# SB_TS_2_00.net
KiCad netlist of a schematic drawn in EAGLE
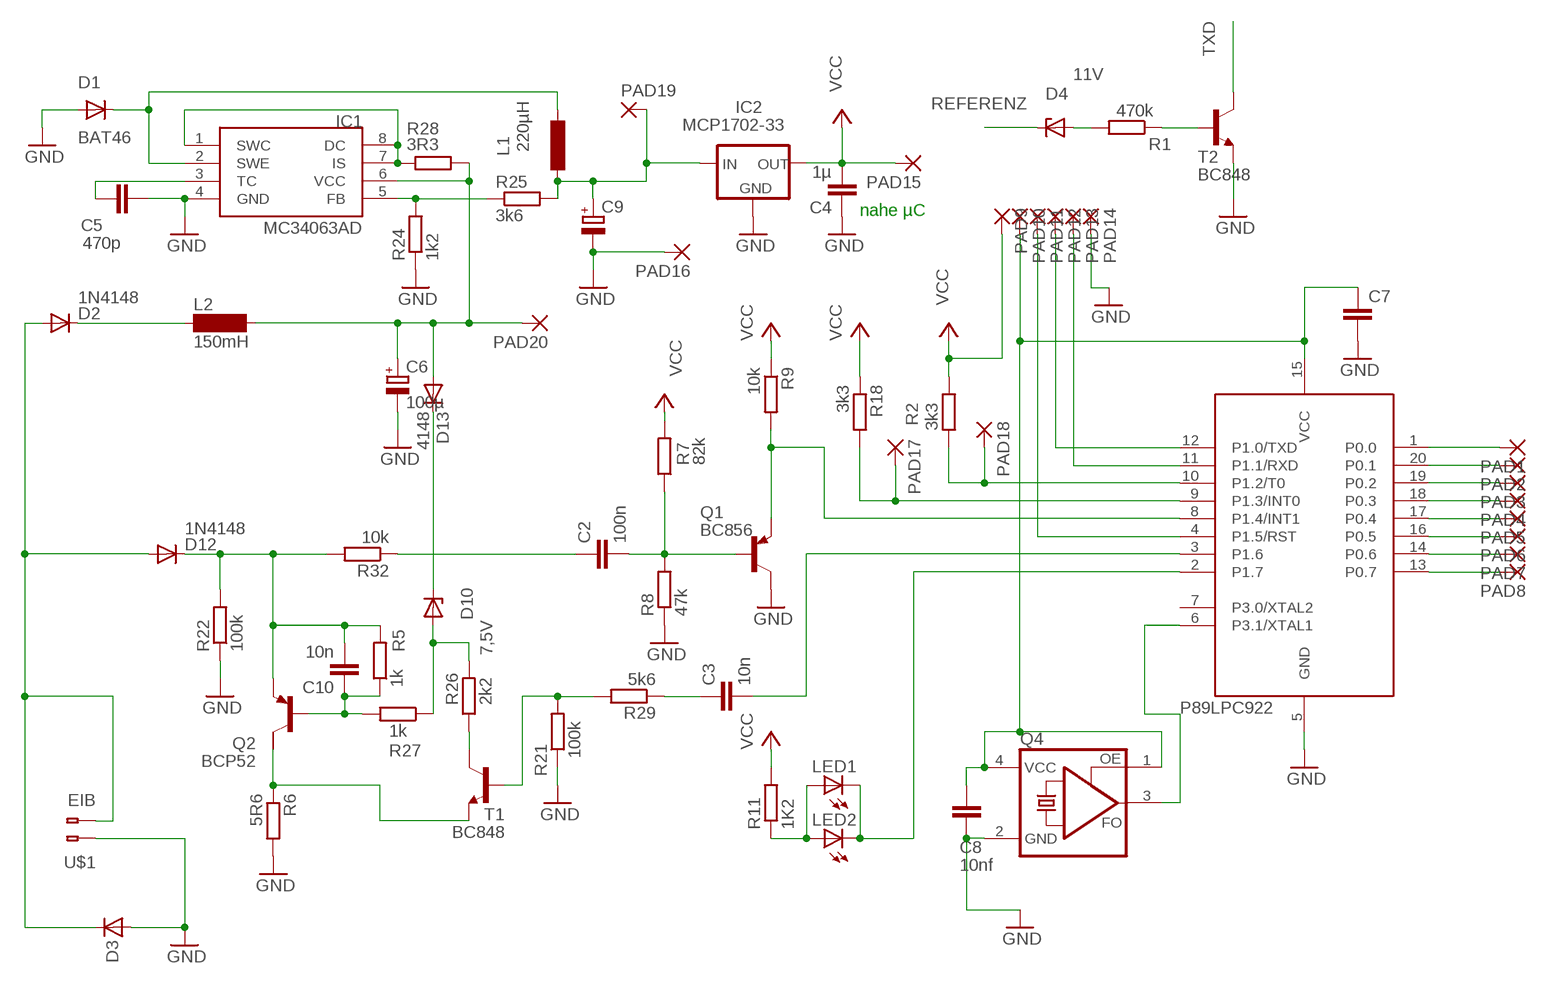
[diagram p0: schematic, sheet 1]

(export (version "E")
  (design (tool "Eeschema 10.0.6"))
  (components
    (comp (ref "C2")
      (value "100n")
      (footprint "eagle-import:C1206")
      (libsource (lib "eagle-import") (part "C-EUC1206"))
    )
    (comp (ref "C3")
      (value "10n")
      (footprint "eagle-import:C1206")
      (libsource (lib "eagle-import") (part "C-EUC1206"))
    )
    (comp (ref "C4")
      (value "1µ")
      (footprint "eagle-import:C1206")
      (libsource (lib "eagle-import") (part "C-EUC1206"))
    )
    (comp (ref "C5")
      (value "470p")
      (footprint "eagle-import:C1206")
      (libsource (lib "eagle-import") (part "C-EUC1206"))
    )
    (comp (ref "C6")
      (value "100µ")
      (footprint "eagle-import:SANYO-OSCON_SMD_C6")
      (libsource (lib "eagle-import") (part "CPOL-EUSANYO_SMD_C6"))
    )
    (comp (ref "C7")
      (value "C-EUC1206")
      (footprint "eagle-import:C1206")
      (libsource (lib "eagle-import") (part "C-EUC1206"))
    )
    (comp (ref "C8")
      (value "10nf")
      (footprint "eagle-import:C1206")
      (libsource (lib "eagle-import") (part "C-EUC1206"))
    )
    (comp (ref "C9")
      (value "CPOL-EUE2.5-5")
      (footprint "eagle-import:E2,5-5")
      (libsource (lib "eagle-import") (part "CPOL-EUE2.5-5"))
    )
    (comp (ref "C10")
      (value "10n")
      (footprint "eagle-import:C1206")
      (libsource (lib "eagle-import") (part "C-EUC1206"))
    )
    (comp (ref "D1")
      (value "BAT46")
      (footprint "eagle-import:MINIMELF")
      (libsource (lib "eagle-import") (part "DIODE-MINIMELF"))
    )
    (comp (ref "D2")
      (value "1N4148")
      (footprint "eagle-import:MINIMELF")
      (libsource (lib "eagle-import") (part "DIODE-MINIMELF"))
    )
    (comp (ref "D3")
      (value "SMAJ40AC")
      (footprint "eagle-import:SMB")
      (libsource (lib "eagle-import") (part "D-SMB"))
    )
    (comp (ref "D4")
      (value "11V")
      (footprint "eagle-import:MINIMELF")
      (libsource (lib "eagle-import") (part "ZPD"))
    )
    (comp (ref "D10")
      (value "7,5V")
      (footprint "eagle-import:MINIMELF")
      (libsource (lib "eagle-import") (part "ZPD"))
    )
    (comp (ref "D12")
      (value "1N4148")
      (footprint "eagle-import:MINIMELF")
      (libsource (lib "eagle-import") (part "DIODE-MINIMELF"))
    )
    (comp (ref "D13")
      (value "4148")
      (footprint "eagle-import:MINIMELF")
      (libsource (lib "eagle-import") (part "DIODE-MINIMELF"))
    )
    (comp (ref "IC1")
      (value "MC34063AD")
      (footprint "eagle-import:SOIC8")
      (libsource (lib "eagle-import") (part "MC34063AD"))
    )
    (comp (ref "IC2")
      (value "MCP1702-33")
      (footprint "eagle-import:79LXX")
      (libsource (lib "eagle-import") (part "79LXX"))
    )
    (comp (ref "IC3")
      (value "LPC922FDH")
      (footprint "eagle-import:TSSOP20")
      (libsource (lib "eagle-import") (part "LPC922FDH"))
    )
    (comp (ref "L1")
      (value "220µH")
      (footprint "eagle-import:2200-11.43")
      (libsource (lib "eagle-import") (part "L-EU2200-11.43"))
    )
    (comp (ref "L2")
      (value "150mH")
      (footprint "eagle-import:SD12_1000")
      (libsource (lib "eagle-import") (part "SD12-1000"))
    )
    (comp (ref "LED1")
      (value "LEDCHIPLED_1206")
      (footprint "eagle-import:CHIPLED_1206")
      (libsource (lib "eagle-import") (part "LEDCHIPLED_1206"))
    )
    (comp (ref "LED2")
      (value "LED3MM")
      (footprint "eagle-import:LED3MM")
      (libsource (lib "eagle-import") (part "LED3MM"))
    )
    (comp (ref "PAD1")
      (value "SMD2")
      (footprint "eagle-import:SMD1,27-2,54")
      (libsource (lib "eagle-import") (part "SMD2"))
    )
    (comp (ref "PAD2")
      (value "SMD2")
      (footprint "eagle-import:SMD1,27-2,54")
      (libsource (lib "eagle-import") (part "SMD2"))
    )
    (comp (ref "PAD3")
      (value "SMD2")
      (footprint "eagle-import:SMD1,27-2,54")
      (libsource (lib "eagle-import") (part "SMD2"))
    )
    (comp (ref "PAD4")
      (value "SMD2")
      (footprint "eagle-import:SMD1,27-2,54")
      (libsource (lib "eagle-import") (part "SMD2"))
    )
    (comp (ref "PAD5")
      (value "SMD2")
      (footprint "eagle-import:SMD1,27-2,54")
      (libsource (lib "eagle-import") (part "SMD2"))
    )
    (comp (ref "PAD6")
      (value "SMD2")
      (footprint "eagle-import:SMD1,27-2,54")
      (libsource (lib "eagle-import") (part "SMD2"))
    )
    (comp (ref "PAD7")
      (value "SMD2")
      (footprint "eagle-import:SMD1,27-2,54")
      (libsource (lib "eagle-import") (part "SMD2"))
    )
    (comp (ref "PAD8")
      (value "SMD2")
      (footprint "eagle-import:SMD1,27-2,54")
      (libsource (lib "eagle-import") (part "SMD2"))
    )
    (comp (ref "PAD9")
      (value "SMD2")
      (footprint "eagle-import:SMD1,27-2,54")
      (libsource (lib "eagle-import") (part "SMD2"))
    )
    (comp (ref "PAD10")
      (value "SMD2")
      (footprint "eagle-import:SMD1,27-2,54")
      (libsource (lib "eagle-import") (part "SMD2"))
    )
    (comp (ref "PAD11")
      (value "SMD2")
      (footprint "eagle-import:SMD1,27-2,54")
      (libsource (lib "eagle-import") (part "SMD2"))
    )
    (comp (ref "PAD12")
      (value "SMD2")
      (footprint "eagle-import:SMD1,27-2,54")
      (libsource (lib "eagle-import") (part "SMD2"))
    )
    (comp (ref "PAD13")
      (value "SMD2")
      (footprint "eagle-import:SMD1,27-2,54")
      (libsource (lib "eagle-import") (part "SMD2"))
    )
    (comp (ref "PAD14")
      (value "SMD2")
      (footprint "eagle-import:SMD1,27-2,54")
      (libsource (lib "eagle-import") (part "SMD2"))
    )
    (comp (ref "PAD15")
      (value "SMD2")
      (footprint "eagle-import:SMD1,27-2,54")
      (libsource (lib "eagle-import") (part "SMD2"))
    )
    (comp (ref "PAD16")
      (value "SMD2")
      (footprint "eagle-import:SMD1,27-2,54")
      (libsource (lib "eagle-import") (part "SMD2"))
    )
    (comp (ref "PAD17")
      (value "SMD2")
      (footprint "eagle-import:SMD1,27-2,54")
      (libsource (lib "eagle-import") (part "SMD2"))
    )
    (comp (ref "PAD18")
      (value "SMD2")
      (footprint "eagle-import:SMD1,27-2,54")
      (libsource (lib "eagle-import") (part "SMD2"))
    )
    (comp (ref "PAD19")
      (value "SMD2")
      (footprint "eagle-import:SMD1,27-2,54")
      (libsource (lib "eagle-import") (part "SMD2"))
    )
    (comp (ref "PAD20")
      (value "SMD2")
      (footprint "eagle-import:SMD1,27-2,54")
      (libsource (lib "eagle-import") (part "SMD2"))
    )
    (comp (ref "Q1")
      (value "BC856")
      (footprint "eagle-import:SOT23-BEC")
      (libsource (lib "eagle-import") (part "BC856SMDALT1"))
    )
    (comp (ref "Q2")
      (value "BCP52")
      (footprint "eagle-import:SOT223")
      (libsource (lib "eagle-import") (part "FZT753SMD"))
    )
    (comp (ref "Q4")
      (value "ASFL")
      (footprint "eagle-import:ASF")
      (libsource (lib "eagle-import") (part "ASFL"))
    )
    (comp (ref "R1")
      (value "470k")
      (footprint "eagle-import:R1206")
      (libsource (lib "eagle-import") (part "R-EU_R1206"))
    )
    (comp (ref "R2")
      (value "3k3")
      (footprint "eagle-import:M1206")
      (libsource (lib "eagle-import") (part "R-EU_M1206"))
    )
    (comp (ref "R5")
      (value "1k")
      (footprint "eagle-import:R1206")
      (libsource (lib "eagle-import") (part "R-EU_R1206"))
    )
    (comp (ref "R6")
      (value "5R6")
      (footprint "eagle-import:R1206")
      (libsource (lib "eagle-import") (part "R-EU_R1206"))
    )
    (comp (ref "R7")
      (value "82k")
      (footprint "eagle-import:R1206")
      (libsource (lib "eagle-import") (part "R-EU_R1206"))
    )
    (comp (ref "R8")
      (value "47k")
      (footprint "eagle-import:M1206")
      (libsource (lib "eagle-import") (part "R-EU_M1206"))
    )
    (comp (ref "R9")
      (value "10k")
      (footprint "eagle-import:R1206")
      (libsource (lib "eagle-import") (part "R-EU_R1206"))
    )
    (comp (ref "R11")
      (value "1K2")
      (footprint "eagle-import:R1206")
      (libsource (lib "eagle-import") (part "R-EU_R1206"))
    )
    (comp (ref "R18")
      (value "3k3")
      (footprint "eagle-import:R1206")
      (libsource (lib "eagle-import") (part "R-EU_R1206"))
    )
    (comp (ref "R21")
      (value "100k")
      (footprint "eagle-import:R1206")
      (libsource (lib "eagle-import") (part "R-EU_R1206"))
    )
    (comp (ref "R22")
      (value "100k")
      (footprint "eagle-import:M1206")
      (libsource (lib "eagle-import") (part "R-EU_M1206"))
    )
    (comp (ref "R24")
      (value "1k2")
      (footprint "eagle-import:R1206")
      (libsource (lib "eagle-import") (part "R-EU_R1206"))
    )
    (comp (ref "R25")
      (value "3k6")
      (footprint "eagle-import:M1206")
      (libsource (lib "eagle-import") (part "R-EU_M1206"))
    )
    (comp (ref "R26")
      (value "2k2")
      (footprint "eagle-import:M1206")
      (libsource (lib "eagle-import") (part "R-EU_M1206"))
    )
    (comp (ref "R27")
      (value "1k")
      (footprint "eagle-import:R1206")
      (libsource (lib "eagle-import") (part "R-EU_R1206"))
    )
    (comp (ref "R28")
      (value "3R3")
      (footprint "eagle-import:M1206")
      (libsource (lib "eagle-import") (part "R-EU_M1206"))
    )
    (comp (ref "R29")
      (value "5k6")
      (footprint "eagle-import:R1206")
      (libsource (lib "eagle-import") (part "R-EU_R1206"))
    )
    (comp (ref "R32")
      (value "10k")
      (footprint "eagle-import:R1206")
      (libsource (lib "eagle-import") (part "R-EU_R1206"))
    )
    (comp (ref "T1")
      (value "BC848")
      (footprint "eagle-import:SOT23")
      (libsource (lib "eagle-import") (part "BC848"))
    )
    (comp (ref "T2")
      (value "BC848")
      (footprint "eagle-import:SOT23")
      (libsource (lib "eagle-import") (part "BC848"))
    )
    (comp (ref "U$1")
      (value "EIB")
      (footprint "eagle-import:BUSKLEMME243-724")
      (libsource (lib "eagle-import") (part "EIB"))
    )
  )
  (nets
    (net (code "1") (name "/REFERENZ") (class "Default")
      (node (ref "D10") (pin "A") (pinfunction "A_A") (pintype "passive"))
      (node (ref "D4") (pin "C") (pinfunction "C_C") (pintype "passive"))
      (node (ref "R26") (pin "2") (pinfunction "2_2") (pintype "passive"))
      (node (ref "R27") (pin "1") (pinfunction "1_1") (pintype "passive"))
    )
    (net (code "2") (name "/TXD") (class "Default")
      (node (ref "IC3") (pin "12") (pinfunction "P1.0/TXD_12") (pintype "bidirectional"))
      (node (ref "PAD12") (pin "1") (pinfunction "P_1") (pintype "passive"))
      (node (ref "T2") (pin "3") (pinfunction "C_3") (pintype "passive"))
    )
    (net (code "3") (name "GND") (class "Default")
      (node (ref "C4") (pin "1") (pinfunction "1_1") (pintype "passive"))
      (node (ref "C5") (pin "2") (pinfunction "2_2") (pintype "passive"))
      (node (ref "C6") (pin "-") (pinfunction "-_-") (pintype "passive"))
      (node (ref "C7") (pin "2") (pinfunction "2_2") (pintype "passive"))
      (node (ref "C8") (pin "2") (pinfunction "2_2") (pintype "passive"))
      (node (ref "C9") (pin "-") (pinfunction "-_-") (pintype "passive"))
      (node (ref "D1") (pin "A") (pinfunction "A_A") (pintype "passive"))
      (node (ref "D3") (pin "2") (pinfunction "A_2") (pintype "passive"))
      (node (ref "IC1") (pin "4") (pinfunction "GND_4") (pintype "passive"))
      (node (ref "IC2") (pin "GND") (pinfunction "GND_GND") (pintype "input"))
      (node (ref "IC3") (pin "5") (pinfunction "GND_5") (pintype "bidirectional"))
      (node (ref "PAD14") (pin "1") (pinfunction "P_1") (pintype "passive"))
      (node (ref "PAD16") (pin "1") (pinfunction "P_1") (pintype "passive"))
      (node (ref "Q1") (pin "C") (pinfunction "C_C") (pintype "passive"))
      (node (ref "Q4") (pin "2") (pinfunction "GND_2") (pintype "power_in"))
      (node (ref "R21") (pin "1") (pinfunction "1_1") (pintype "passive"))
      (node (ref "R22") (pin "1") (pinfunction "1_1") (pintype "passive"))
      (node (ref "R24") (pin "1") (pinfunction "1_1") (pintype "passive"))
      (node (ref "R6") (pin "2") (pinfunction "2_2") (pintype "passive"))
      (node (ref "R8") (pin "1") (pinfunction "1_1") (pintype "passive"))
      (node (ref "T2") (pin "2") (pinfunction "E_2") (pintype "passive"))
      (node (ref "U$1") (pin "1") (pinfunction "B-1_1") (pintype "passive"))
    )
    (net (code "4") (name "Net-(C2-Pad1)") (class "Default")
      (node (ref "C2") (pin "1") (pinfunction "1_1") (pintype "passive"))
      (node (ref "R32") (pin "1") (pinfunction "1_1") (pintype "passive"))
    )
    (net (code "5") (name "Net-(C2-Pad2)") (class "Default")
      (node (ref "C2") (pin "2") (pinfunction "2_2") (pintype "passive"))
      (node (ref "Q1") (pin "B") (pinfunction "B_B") (pintype "passive"))
      (node (ref "R7") (pin "1") (pinfunction "1_1") (pintype "passive"))
      (node (ref "R8") (pin "2") (pinfunction "2_2") (pintype "passive"))
    )
    (net (code "6") (name "Net-(C3-Pad1)") (class "Default")
      (node (ref "C3") (pin "1") (pinfunction "1_1") (pintype "passive"))
      (node (ref "R29") (pin "1") (pinfunction "1_1") (pintype "passive"))
    )
    (net (code "7") (name "Net-(D2-PadC)") (class "Default")
      (node (ref "D2") (pin "C") (pinfunction "C_C") (pintype "passive"))
      (node (ref "L2") (pin "1") (pinfunction "1_1") (pintype "passive"))
    )
    (net (code "8") (name "Net-(D3-C)") (class "Default")
      (node (ref "D12") (pin "A") (pinfunction "A_A") (pintype "passive"))
      (node (ref "D2") (pin "A") (pinfunction "A_A") (pintype "passive"))
      (node (ref "D3") (pin "1") (pinfunction "C_1") (pintype "passive"))
      (node (ref "U$1") (pin "2") (pinfunction "B-2_2") (pintype "passive"))
    )
    (net (code "9") (name "Net-(D4-PadA)") (class "Default")
      (node (ref "D4") (pin "A") (pinfunction "A_A") (pintype "passive"))
      (node (ref "R1") (pin "2") (pinfunction "2_2") (pintype "passive"))
    )
    (net (code "10") (name "Net-(D10-PadC)") (class "Default")
      (node (ref "D10") (pin "C") (pinfunction "C_C") (pintype "passive"))
      (node (ref "D13") (pin "C") (pinfunction "C_C") (pintype "passive"))
    )
    (net (code "11") (name "Net-(IC1-DC)") (class "Default")
      (node (ref "IC1") (pin "1") (pinfunction "SWC_1") (pintype "passive"))
      (node (ref "IC1") (pin "7") (pinfunction "IS_7") (pintype "passive"))
      (node (ref "IC1") (pin "8") (pinfunction "DC_8") (pintype "passive"))
      (node (ref "R28") (pin "1") (pinfunction "1_1") (pintype "passive"))
    )
    (net (code "12") (name "Net-(IC1-FB)") (class "Default")
      (node (ref "IC1") (pin "5") (pinfunction "FB_5") (pintype "passive"))
      (node (ref "R24") (pin "2") (pinfunction "2_2") (pintype "passive"))
      (node (ref "R25") (pin "1") (pinfunction "1_1") (pintype "passive"))
    )
    (net (code "13") (name "Net-(IC1-SWE)") (class "Default")
      (node (ref "D1") (pin "C") (pinfunction "C_C") (pintype "passive"))
      (node (ref "IC1") (pin "2") (pinfunction "SWE_2") (pintype "passive"))
      (node (ref "L1") (pin "2") (pinfunction "2_2") (pintype "passive"))
    )
    (net (code "14") (name "Net-(IC1-TC)") (class "Default")
      (node (ref "C5") (pin "1") (pinfunction "1_1") (pintype "passive"))
      (node (ref "IC1") (pin "3") (pinfunction "TC_3") (pintype "passive"))
    )
    (net (code "15") (name "Net-(IC1-VCC)") (class "Default")
      (node (ref "C6") (pin "+") (pinfunction "+_+") (pintype "passive"))
      (node (ref "D13") (pin "A") (pinfunction "A_A") (pintype "passive"))
      (node (ref "IC1") (pin "6") (pinfunction "VCC_6") (pintype "passive"))
      (node (ref "L2") (pin "2") (pinfunction "2_2") (pintype "passive"))
      (node (ref "PAD20") (pin "1") (pinfunction "P_1") (pintype "passive"))
      (node (ref "R28") (pin "2") (pinfunction "2_2") (pintype "passive"))
    )
    (net (code "16") (name "Net-(IC3-P0.0)") (class "Default")
      (node (ref "IC3") (pin "1") (pinfunction "P0.0_1") (pintype "bidirectional"))
      (node (ref "PAD1") (pin "1") (pinfunction "P_1") (pintype "passive"))
    )
    (net (code "17") (name "Net-(IC3-P0.1)") (class "Default")
      (node (ref "IC3") (pin "20") (pinfunction "P0.1_20") (pintype "bidirectional"))
      (node (ref "PAD2") (pin "1") (pinfunction "P_1") (pintype "passive"))
    )
    (net (code "18") (name "Net-(IC3-P0.2)") (class "Default")
      (node (ref "IC3") (pin "19") (pinfunction "P0.2_19") (pintype "bidirectional"))
      (node (ref "PAD3") (pin "1") (pinfunction "P_1") (pintype "passive"))
    )
    (net (code "19") (name "Net-(IC3-P0.3)") (class "Default")
      (node (ref "IC3") (pin "18") (pinfunction "P0.3_18") (pintype "bidirectional"))
      (node (ref "PAD4") (pin "1") (pinfunction "P_1") (pintype "passive"))
    )
    (net (code "20") (name "Net-(IC3-P0.4)") (class "Default")
      (node (ref "IC3") (pin "17") (pinfunction "P0.4_17") (pintype "bidirectional"))
      (node (ref "PAD5") (pin "1") (pinfunction "P_1") (pintype "passive"))
    )
    (net (code "21") (name "Net-(IC3-P0.5)") (class "Default")
      (node (ref "IC3") (pin "16") (pinfunction "P0.5_16") (pintype "bidirectional"))
      (node (ref "PAD6") (pin "1") (pinfunction "P_1") (pintype "passive"))
    )
    (net (code "22") (name "Net-(IC3-P0.6)") (class "Default")
      (node (ref "IC3") (pin "14") (pinfunction "P0.6_14") (pintype "bidirectional"))
      (node (ref "PAD7") (pin "1") (pinfunction "P_1") (pintype "passive"))
    )
    (net (code "23") (name "Net-(IC3-P0.7)") (class "Default")
      (node (ref "IC3") (pin "13") (pinfunction "P0.7_13") (pintype "bidirectional"))
      (node (ref "PAD8") (pin "1") (pinfunction "P_1") (pintype "passive"))
    )
    (net (code "24") (name "Net-(IC3-P1.1{slash}RXD)") (class "Default")
      (node (ref "IC3") (pin "11") (pinfunction "P1.1/RXD_11") (pintype "bidirectional"))
      (node (ref "PAD13") (pin "1") (pinfunction "P_1") (pintype "passive"))
    )
    (net (code "25") (name "Net-(IC3-P1.2{slash}T0)") (class "Default")
      (node (ref "IC3") (pin "10") (pinfunction "P1.2/T0_10") (pintype "bidirectional"))
      (node (ref "PAD18") (pin "1") (pinfunction "P_1") (pintype "passive"))
      (node (ref "R2") (pin "2") (pinfunction "2_2") (pintype "passive"))
    )
    (net (code "26") (name "Net-(IC3-P1.3{slash}INT0)") (class "Default")
      (node (ref "IC3") (pin "9") (pinfunction "P1.3/INT0_9") (pintype "bidirectional"))
      (node (ref "PAD17") (pin "1") (pinfunction "P_1") (pintype "passive"))
      (node (ref "R18") (pin "2") (pinfunction "2_2") (pintype "passive"))
    )
    (net (code "27") (name "Net-(IC3-P1.4{slash}INT1)") (class "Default")
      (node (ref "IC3") (pin "8") (pinfunction "P1.4/INT1_8") (pintype "bidirectional"))
      (node (ref "Q1") (pin "E") (pinfunction "E_E") (pintype "passive"))
      (node (ref "R9") (pin "2") (pinfunction "2_2") (pintype "passive"))
    )
    (net (code "28") (name "Net-(IC3-P1.5{slash}RST)") (class "Default")
      (node (ref "IC3") (pin "4") (pinfunction "P1.5/RST_4") (pintype "bidirectional"))
      (node (ref "PAD11") (pin "1") (pinfunction "P_1") (pintype "passive"))
    )
    (net (code "29") (name "Net-(IC3-P1.6)") (class "Default")
      (node (ref "C3") (pin "2") (pinfunction "2_2") (pintype "passive"))
      (node (ref "IC3") (pin "3") (pinfunction "P1.6_3") (pintype "bidirectional"))
    )
    (net (code "30") (name "Net-(IC3-P1.7)") (class "Default")
      (node (ref "IC3") (pin "2") (pinfunction "P1.7_2") (pintype "bidirectional"))
      (node (ref "LED1") (pin "C") (pinfunction "C_C") (pintype "passive"))
      (node (ref "LED2") (pin "K") (pinfunction "C_K") (pintype "passive"))
    )
    (net (code "31") (name "Net-(IC3-P3.1{slash}XTAL1)") (class "Default")
      (node (ref "IC3") (pin "6") (pinfunction "P3.1/XTAL1_6") (pintype "bidirectional"))
      (node (ref "Q4") (pin "3") (pinfunction "FO_3") (pintype "output"))
    )
    (net (code "32") (name "Net-(IC3-VCC)") (class "Default")
      (node (ref "C7") (pin "1") (pinfunction "1_1") (pintype "passive"))
      (node (ref "C8") (pin "1") (pinfunction "1_1") (pintype "passive"))
      (node (ref "IC3") (pin "15") (pinfunction "VCC_15") (pintype "bidirectional"))
      (node (ref "PAD10") (pin "1") (pinfunction "P_1") (pintype "passive"))
      (node (ref "Q4") (pin "1") (pinfunction "OE_1") (pintype "input"))
      (node (ref "Q4") (pin "4") (pinfunction "VCC_4") (pintype "power_in"))
    )
    (net (code "33") (name "Net-(LED1-PadA)") (class "Default")
      (node (ref "LED1") (pin "A") (pinfunction "A_A") (pintype "passive"))
      (node (ref "LED2") (pin "A") (pinfunction "A_A") (pintype "passive"))
      (node (ref "R11") (pin "1") (pinfunction "1_1") (pintype "passive"))
    )
    (net (code "34") (name "Net-(PAD19-P)") (class "Default")
      (node (ref "C9") (pin "+") (pinfunction "+_+") (pintype "passive"))
      (node (ref "IC2") (pin "IN") (pinfunction "IN_IN") (pintype "input"))
      (node (ref "L1") (pin "1") (pinfunction "1_1") (pintype "passive"))
      (node (ref "PAD19") (pin "1") (pinfunction "P_1") (pintype "passive"))
      (node (ref "R25") (pin "2") (pinfunction "2_2") (pintype "passive"))
    )
    (net (code "35") (name "Net-(Q2-B)") (class "Default")
      (node (ref "C10") (pin "1") (pinfunction "1_1") (pintype "passive"))
      (node (ref "Q2") (pin "1") (pinfunction "B_1") (pintype "passive"))
      (node (ref "R27") (pin "2") (pinfunction "2_2") (pintype "passive"))
      (node (ref "R5") (pin "1") (pinfunction "1_1") (pintype "passive"))
    )
    (net (code "36") (name "Net-(Q2-C)") (class "Default")
      (node (ref "Q2") (pin "2") (pinfunction "C_2") (pintype "passive"))
      (node (ref "R6") (pin "1") (pinfunction "1_1") (pintype "passive"))
      (node (ref "T1") (pin "2") (pinfunction "E_2") (pintype "passive"))
    )
    (net (code "37") (name "Net-(Q2-E)") (class "Default")
      (node (ref "C10") (pin "2") (pinfunction "2_2") (pintype "passive"))
      (node (ref "D12") (pin "C") (pinfunction "C_C") (pintype "passive"))
      (node (ref "Q2") (pin "3") (pinfunction "E_3") (pintype "passive"))
      (node (ref "R22") (pin "2") (pinfunction "2_2") (pintype "passive"))
      (node (ref "R32") (pin "2") (pinfunction "2_2") (pintype "passive"))
      (node (ref "R5") (pin "2") (pinfunction "2_2") (pintype "passive"))
    )
    (net (code "38") (name "Net-(T1-B)") (class "Default")
      (node (ref "R21") (pin "2") (pinfunction "2_2") (pintype "passive"))
      (node (ref "R29") (pin "2") (pinfunction "2_2") (pintype "passive"))
      (node (ref "T1") (pin "1") (pinfunction "B_1") (pintype "passive"))
    )
    (net (code "39") (name "Net-(T1-C)") (class "Default")
      (node (ref "R26") (pin "1") (pinfunction "1_1") (pintype "passive"))
      (node (ref "T1") (pin "3") (pinfunction "C_3") (pintype "passive"))
    )
    (net (code "40") (name "Net-(T2-B)") (class "Default")
      (node (ref "R1") (pin "1") (pinfunction "1_1") (pintype "passive"))
      (node (ref "T2") (pin "1") (pinfunction "B_1") (pintype "passive"))
    )
    (net (code "41") (name "VCC") (class "Default")
      (node (ref "C4") (pin "2") (pinfunction "2_2") (pintype "passive"))
      (node (ref "IC2") (pin "OUT") (pinfunction "OUT_OUT") (pintype "passive"))
      (node (ref "PAD15") (pin "1") (pinfunction "P_1") (pintype "passive"))
      (node (ref "PAD9") (pin "1") (pinfunction "P_1") (pintype "passive"))
      (node (ref "R11") (pin "2") (pinfunction "2_2") (pintype "passive"))
      (node (ref "R18") (pin "1") (pinfunction "1_1") (pintype "passive"))
      (node (ref "R2") (pin "1") (pinfunction "1_1") (pintype "passive"))
      (node (ref "R7") (pin "2") (pinfunction "2_2") (pintype "passive"))
      (node (ref "R9") (pin "1") (pinfunction "1_1") (pintype "passive"))
    )
    (net (code "42") (name "unconnected-(IC3-P3.0{slash}XTAL2-Pad7)") (class "Default")
      (node (ref "IC3") (pin "7") (pinfunction "P3.0/XTAL2_7") (pintype "bidirectional"))
    )
    (net (code "43") (name "unconnected-(Q2-C{slash}-Pad4)") (class "Default")
      (node (ref "Q2") (pin "4") (pinfunction "C/_4") (pintype "passive"))
    )
  )
)
